# BBB_LEDs.net
KiCad netlist of a schematic drawn in EAGLE
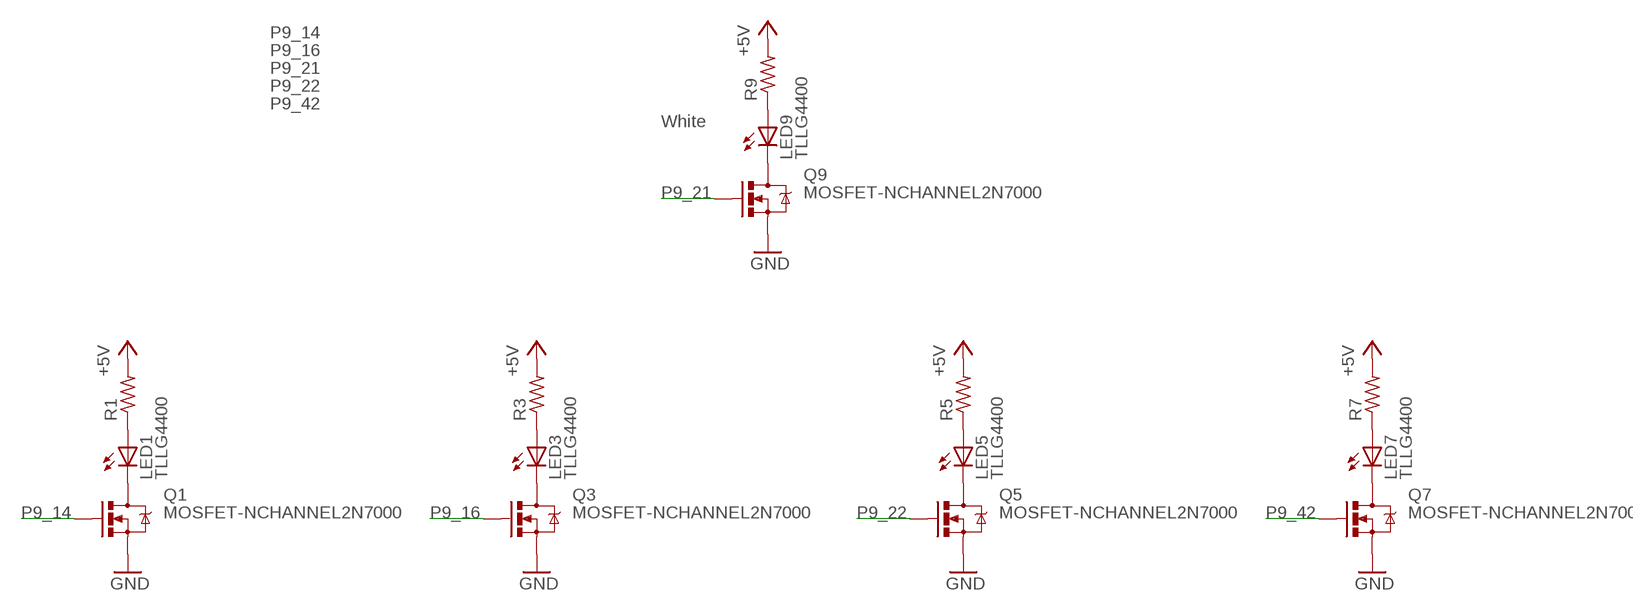
[diagram p0: schematic, sheet 1]

(export (version "E")
  (design (tool "Eeschema 10.0.6"))
  (components
    (comp (ref "LED1")
      (value "TLLG4400")
      (footprint "eagle-import:LED3MM")
      (fields (field (name "MF") "VISHAY SEMICONDUCTOR"))
      (libsource (lib "eagle-import") (part "TLLG4400"))
    )
    (comp (ref "LED3")
      (value "TLLG4400")
      (footprint "eagle-import:LED3MM")
      (fields (field (name "MF") "VISHAY SEMICONDUCTOR"))
      (libsource (lib "eagle-import") (part "TLLG4400"))
    )
    (comp (ref "LED5")
      (value "TLLG4400")
      (footprint "eagle-import:LED3MM")
      (fields (field (name "MF") "VISHAY SEMICONDUCTOR"))
      (libsource (lib "eagle-import") (part "TLLG4400"))
    )
    (comp (ref "LED7")
      (value "TLLG4400")
      (footprint "eagle-import:LED3MM")
      (fields (field (name "MF") "VISHAY SEMICONDUCTOR"))
      (libsource (lib "eagle-import") (part "TLLG4400"))
    )
    (comp (ref "LED9")
      (value "TLLG4400")
      (footprint "eagle-import:LED3MM")
      (fields (field (name "MF") "VISHAY SEMICONDUCTOR"))
      (libsource (lib "eagle-import") (part "TLLG4400"))
    )
    (comp (ref "Q1")
      (value "MOSFET-NCHANNEL2N7000")
      (footprint "eagle-import:TO-92")
      (libsource (lib "eagle-import") (part "MOSFET-NCHANNEL2N7000"))
    )
    (comp (ref "Q3")
      (value "MOSFET-NCHANNEL2N7000")
      (footprint "eagle-import:TO-92")
      (libsource (lib "eagle-import") (part "MOSFET-NCHANNEL2N7000"))
    )
    (comp (ref "Q5")
      (value "MOSFET-NCHANNEL2N7000")
      (footprint "eagle-import:TO-92")
      (libsource (lib "eagle-import") (part "MOSFET-NCHANNEL2N7000"))
    )
    (comp (ref "Q7")
      (value "MOSFET-NCHANNEL2N7000")
      (footprint "eagle-import:TO-92")
      (libsource (lib "eagle-import") (part "MOSFET-NCHANNEL2N7000"))
    )
    (comp (ref "Q9")
      (value "MOSFET-NCHANNEL2N7000")
      (footprint "eagle-import:TO-92")
      (libsource (lib "eagle-import") (part "MOSFET-NCHANNEL2N7000"))
    )
    (comp (ref "R1")
      (value "R-US_0207/10")
      (footprint "eagle-import:0207_10")
      (libsource (lib "eagle-import") (part "R-US_0207/10"))
    )
    (comp (ref "R3")
      (value "R-US_0207/10")
      (footprint "eagle-import:0207_10")
      (libsource (lib "eagle-import") (part "R-US_0207/10"))
    )
    (comp (ref "R5")
      (value "R-US_0207/10")
      (footprint "eagle-import:0207_10")
      (libsource (lib "eagle-import") (part "R-US_0207/10"))
    )
    (comp (ref "R7")
      (value "R-US_0207/10")
      (footprint "eagle-import:0207_10")
      (libsource (lib "eagle-import") (part "R-US_0207/10"))
    )
    (comp (ref "R9")
      (value "R-US_0207/10")
      (footprint "eagle-import:0207_10")
      (libsource (lib "eagle-import") (part "R-US_0207/10"))
    )
  )
  (nets
    (net (code "1") (name "+5V") (class "Default")
      (node (ref "R1") (pin "2") (pinfunction "2_2") (pintype "passive"))
      (node (ref "R3") (pin "2") (pinfunction "2_2") (pintype "passive"))
      (node (ref "R5") (pin "2") (pinfunction "2_2") (pintype "passive"))
      (node (ref "R7") (pin "2") (pinfunction "2_2") (pintype "passive"))
      (node (ref "R9") (pin "2") (pinfunction "2_2") (pintype "passive"))
    )
    (net (code "2") (name "/P9_14") (class "Default")
      (node (ref "Q1") (pin "2") (pinfunction "G_2") (pintype "passive"))
    )
    (net (code "3") (name "/P9_16") (class "Default")
      (node (ref "Q3") (pin "2") (pinfunction "G_2") (pintype "passive"))
    )
    (net (code "4") (name "/P9_21") (class "Default")
      (node (ref "Q9") (pin "2") (pinfunction "G_2") (pintype "passive"))
    )
    (net (code "5") (name "/P9_22") (class "Default")
      (node (ref "Q5") (pin "2") (pinfunction "G_2") (pintype "passive"))
    )
    (net (code "6") (name "/P9_42") (class "Default")
      (node (ref "Q7") (pin "2") (pinfunction "G_2") (pintype "passive"))
    )
    (net (code "7") (name "GND") (class "Default")
      (node (ref "Q1") (pin "1") (pinfunction "S_1") (pintype "passive"))
      (node (ref "Q3") (pin "1") (pinfunction "S_1") (pintype "passive"))
      (node (ref "Q5") (pin "1") (pinfunction "S_1") (pintype "passive"))
      (node (ref "Q7") (pin "1") (pinfunction "S_1") (pintype "passive"))
      (node (ref "Q9") (pin "1") (pinfunction "S_1") (pintype "passive"))
    )
    (net (code "8") (name "Net-(LED1-C)") (class "Default")
      (node (ref "LED1") (pin "K") (pinfunction "C_K") (pintype "passive"))
      (node (ref "Q1") (pin "3") (pinfunction "D_3") (pintype "passive"))
    )
    (net (code "9") (name "Net-(LED1-PadA)") (class "Default")
      (node (ref "LED1") (pin "A") (pinfunction "A_A") (pintype "passive"))
      (node (ref "R1") (pin "1") (pinfunction "1_1") (pintype "passive"))
    )
    (net (code "10") (name "Net-(LED3-C)") (class "Default")
      (node (ref "LED3") (pin "K") (pinfunction "C_K") (pintype "passive"))
      (node (ref "Q3") (pin "3") (pinfunction "D_3") (pintype "passive"))
    )
    (net (code "11") (name "Net-(LED3-PadA)") (class "Default")
      (node (ref "LED3") (pin "A") (pinfunction "A_A") (pintype "passive"))
      (node (ref "R3") (pin "1") (pinfunction "1_1") (pintype "passive"))
    )
    (net (code "12") (name "Net-(LED5-C)") (class "Default")
      (node (ref "LED5") (pin "K") (pinfunction "C_K") (pintype "passive"))
      (node (ref "Q5") (pin "3") (pinfunction "D_3") (pintype "passive"))
    )
    (net (code "13") (name "Net-(LED5-PadA)") (class "Default")
      (node (ref "LED5") (pin "A") (pinfunction "A_A") (pintype "passive"))
      (node (ref "R5") (pin "1") (pinfunction "1_1") (pintype "passive"))
    )
    (net (code "14") (name "Net-(LED7-C)") (class "Default")
      (node (ref "LED7") (pin "K") (pinfunction "C_K") (pintype "passive"))
      (node (ref "Q7") (pin "3") (pinfunction "D_3") (pintype "passive"))
    )
    (net (code "15") (name "Net-(LED7-PadA)") (class "Default")
      (node (ref "LED7") (pin "A") (pinfunction "A_A") (pintype "passive"))
      (node (ref "R7") (pin "1") (pinfunction "1_1") (pintype "passive"))
    )
    (net (code "16") (name "Net-(LED9-C)") (class "Default")
      (node (ref "LED9") (pin "K") (pinfunction "C_K") (pintype "passive"))
      (node (ref "Q9") (pin "3") (pinfunction "D_3") (pintype "passive"))
    )
    (net (code "17") (name "Net-(LED9-PadA)") (class "Default")
      (node (ref "LED9") (pin "A") (pinfunction "A_A") (pintype "passive"))
      (node (ref "R9") (pin "1") (pinfunction "1_1") (pintype "passive"))
    )
  )
)
